# Boost_Converter.net
KiCad netlist of a schematic drawn in Altium Designer
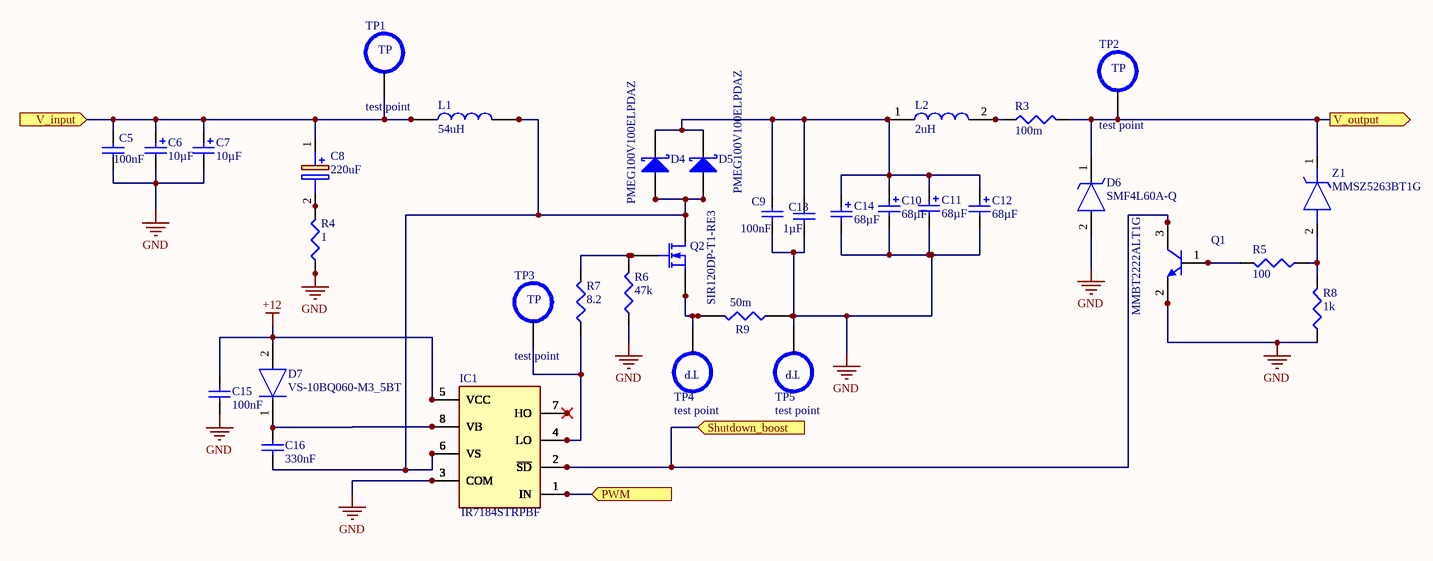
[diagram p0: Boost_Converter.SchDoc]

(export (version "E")
  (design (tool "Eeschema 10.0.6"))
  (components
    (comp (ref "C5")
      (value "100nF")
      (footprint "CAPC3216X180N")
      (description "Capacitor 100nF")
      (fields (field (name "Comment") "CC1206KKX7R0BB104") (field (name "PUBLISHER") "Altium Limited"))
      (libsource (lib "Sch_Capacitors") (part "CC1206KKX7R0BB104"))
    )
    (comp (ref "C6")
      (value "10µF")
      (footprint "870056174001")
      (description "Capacitor Polarised 10uF")
      (fields
        (field (name "MANUFACTURER_PART_NUMBER") "EEV-FK1K101V")
        (field (name "MOUSER PART NUMBER") "667-EEV-FK1K101V")
      )
      (libsource (lib "Sch_Capacitors") (part "870056174001"))
    )
    (comp (ref "C7")
      (value "10µF")
      (footprint "870056174001")
      (description "Capacitor Polarised 10uF")
      (fields
        (field (name "MANUFACTURER_PART_NUMBER") "EEV-FK1K101V")
        (field (name "MOUSER PART NUMBER") "667-EEV-FK1K101V")
      )
      (libsource (lib "Sch_Capacitors") (part "870056174001"))
    )
    (comp (ref "C8")
      (value "220uF")
      (footprint "CAPPRD500W60D1275H2700")
      (description "Capacitor Polarised")
      (fields
        (field (name "MANUFACTURER_PART_NUMBER") "100ZLJ220M12.5X25")
        (field (name "MOUSER PART NUMBER") "232-100ZLJ220M125X25")
      )
      (libsource (lib "Sch_Capacitors") (part "100ZLJ220M12.5X25"))
    )
    (comp (ref "C9")
      (value "100nF")
      (footprint "CAPC3216X180N")
      (description "Capacitor 100nF")
      (fields (field (name "Comment") "CC1206KKX7R0BB104") (field (name "PUBLISHER") "Altium Limited"))
      (libsource (lib "Sch_Capacitors") (part "CC1206KKX7R0BB104"))
    )
    (comp (ref "C10")
      (value "EGXF251ELL680MK30S")
      (footprint "EGXF251ELL680MK30S")
      (description "Capacitor 68uF")
      (fields
        (field (name "MANUFACTURER_PART_NUMBER") "EEV-FK1K101V")
        (field (name "MOUSER PART NUMBER") "667-EEV-FK1K101V")
        (field (name "EGXF251ELL680MK30S") "68µF")
      )
      (libsource (lib "Sch_Capacitors") (part "EGXF251ELL680MK30S"))
    )
    (comp (ref "C11")
      (value "EGXF251ELL680MK30S")
      (footprint "EGXF251ELL680MK30S")
      (description "Capacitor 68uF")
      (fields
        (field (name "MANUFACTURER_PART_NUMBER") "EEV-FK1K101V")
        (field (name "MOUSER PART NUMBER") "667-EEV-FK1K101V")
        (field (name "EGXF251ELL680MK30S") "68µF")
      )
      (libsource (lib "Sch_Capacitors") (part "EGXF251ELL680MK30S"))
    )
    (comp (ref "C12")
      (value "EGXF251ELL680MK30S")
      (footprint "EGXF251ELL680MK30S")
      (description "Capacitor 68uF")
      (fields
        (field (name "MANUFACTURER_PART_NUMBER") "EEV-FK1K101V")
        (field (name "MOUSER PART NUMBER") "667-EEV-FK1K101V")
        (field (name "EGXF251ELL680MK30S") "68µF")
      )
      (libsource (lib "Sch_Capacitors") (part "EGXF251ELL680MK30S"))
    )
    (comp (ref "C13")
      (value "1µF")
      (footprint "CAPC3216X180N")
      (description "Capacitor 1uF")
      (fields (field (name "Comment") "C1206C105M5REC7210") (field (name "PUBLISHER") "Altium Limited"))
      (libsource (lib "Sch_Capacitors") (part "C1206C105M5REC7210"))
    )
    (comp (ref "C14")
      (value "EGXF251ELL680MK30S")
      (footprint "EGXF251ELL680MK30S")
      (description "Capacitor 68uF")
      (fields
        (field (name "MANUFACTURER_PART_NUMBER") "EEV-FK1K101V")
        (field (name "MOUSER PART NUMBER") "667-EEV-FK1K101V")
        (field (name "EGXF251ELL680MK30S") "68µF")
      )
      (libsource (lib "Sch_Capacitors") (part "EGXF251ELL680MK30S"))
    )
    (comp (ref "C15")
      (value "100nF")
      (footprint "CAPC3216X180N")
      (description "Capacitor 100nF")
      (fields (field (name "PUBLISHER") "Altium Limited"))
      (libsource (lib "Sch_Capacitors") (part "CC1206KKX7R0BB104"))
    )
    (comp (ref "C16")
      (value "330nF")
      (footprint "CAPC3216X180N")
      (description "Capacitor 330nF")
      (fields (field (name "PUBLISHER") "Altium Limited"))
      (libsource (lib "Sch_Capacitors") (part "C3216X7R2A334K130AA"))
    )
    (comp (ref "D4")
      (value "PMEG100V100ELPDAZ")
      (footprint "PMEG100V100ELPDAZ")
      (description "Diode")
      (fields (field (name "MOUSER PART NUMBER") "771-MEG100V100ELPDAZ"))
      (libsource (lib "Sch_Diodes") (part "PMEG100V100ELPDAZ"))
    )
    (comp (ref "D5")
      (value "PMEG100V100ELPDAZ")
      (footprint "PMEG100V100ELPDAZ")
      (description "Diode")
      (fields (field (name "MOUSER PART NUMBER") "771-MEG100V100ELPDAZ"))
      (libsource (lib "Sch_Diodes") (part "PMEG100V100ELPDAZ"))
    )
    (comp (ref "D6")
      (value "SMF4L60A-Q")
      (footprint "SODFL3716X135N")
      (description "TVS Diode (Uni-directional)")
      (fields (field (name "MOUSER PART NUMBER") "652-SMF4L60A-Q"))
      (libsource (lib "Sch_Diodes") (part "SMF4L60A-Q"))
    )
    (comp (ref "D7")
      (value "VS-10BQ060-M3_5BT")
      (footprint "DIOM5436X244N")
      (description "Diode")
      (fields
        (field (name "MANUFACTURER_PART_NUMBER") "VS-10BQ060-M3/5BT")
        (field (name "MOUSER PART NUMBER") "78-VS-10BQ060-M35BT")
      )
      (libsource (lib "Sch_Diodes") (part "VS-10BQ060-M3_5BT"))
    )
    (comp (ref "IC1")
      (value "IR7184STRPBF")
      (footprint "SOIC127P600X175-8N")
      (description "Integrated Circuit")
      (fields (field (name "MOUSER PART NUMBER") "942-IR7184STRPBF"))
      (libsource (lib "Sch_IC") (part "IR7184STRPBF"))
    )
    (comp (ref "L1")
      (value "54uH")
      (footprint "SHBC201R7A0054V")
      (description "Inductor 54uH")
      (fields (field (name "Comment") "SHBC20-1R7A0054V"))
      (libsource (lib "Sch_Inductors") (part "SHBC20-1R7A0054V"))
    )
    (comp (ref "L2")
      (value "2uH")
      (footprint "SRP1510CA100M")
      (description "Inductor 2uH")
      (fields
        (field (name "MANUFACTURER_PART_NUMBER") "SRP1038C-100M")
        (field (name "MOUSER PART NUMBER") "652-SRP1038C-100M")
      )
      (libsource (lib "Sch_Inductors") (part "SRP1580CA-2R0M"))
    )
    (comp (ref "Q1")
      (value "MMBT2222ALT1G")
      (footprint "SOT96P237X111-3N")
      (description "NPN transistor")
      (fields (field (name "MOUSER PART NUMBER") "863-MMBT2222ALT1G"))
      (libsource (lib "Sch_Transistors") (part "MMBT2222ALT1G"))
    )
    (comp (ref "Q2")
      (value "SIR120DP-T1-RE3")
      (footprint "SI7141DPT1GE3")
      (description "MOSFET (N-Channel)")
      (fields (field (name "MOUSER PART NUMBER") "78-SIR120DP-T1-RE3"))
      (libsource (lib "Sch_Transistors") (part "SIR120DP-T1-RE3"))
    )
    (comp (ref "R3")
      (value "100m")
      (footprint "RESC6331X80N")
      (description "Resistor 100m")
      (fields (field (name "Comment") "CRM2512-FX-R100ELF") (field (name "PUBLISHER") "Altium Limited"))
      (libsource (lib "Sch_Resistors") (part "CRM2512-FX-R100ELF"))
    )
    (comp (ref "R4")
      (value "1")
      (footprint "RESC6432X120N")
      (description "Resistor 1 3W")
      (fields (field (name "Comment") "35221R0JT") (field (name "PUBLISHER") "Altium Limited"))
      (libsource (lib "Sch_Resistors") (part "35221R0JT"))
    )
    (comp (ref "R5")
      (value "100")
      (footprint "RESC3216X75N")
      (description "Resistor 100")
      (fields (field (name "Comment") "100Ω") (field (name "PUBLISHER") "Altium Limited"))
      (libsource (lib "Sch_Resistors") (part "MCWR12X1000FTL"))
    )
    (comp (ref "R6")
      (value "47k")
      (footprint "RESC3216X75N")
      (description "Resistor 47k")
      (fields (field (name "Comment") "MCWR12X4702FTL") (field (name "PUBLISHER") "Altium Limited"))
      (libsource (lib "Sch_Resistors") (part "MCWR12X4702FTL"))
    )
    (comp (ref "R7")
      (value "8.2")
      (footprint "RESC3216X75N")
      (description "Resistor 8.2")
      (fields (field (name "Comment") "MCWR12W8R20FTL") (field (name "PUBLISHER") "Altium Limited"))
      (libsource (lib "Sch_Resistors") (part "MCWR12W8R20FTL"))
    )
    (comp (ref "R8")
      (value "1k")
      (footprint "RESC3216X75N")
      (description "Resistor 1k")
      (fields (field (name "Comment") "1KΩ") (field (name "PUBLISHER") "Altium Limited"))
      (libsource (lib "Sch_Resistors") (part "MCHP06W2F1001T5E"))
    )
    (comp (ref "R9")
      (value "50m")
      (footprint "RESC7146X175N")
      (description "Resistor 50m")
      (fields
        (field (name "MANUFACTURER_PART_NUMBER") "WSHM2818R0500FEB")
        (field (name "MOUSER PART NUMBER") "71-WSHM2818R0500FEB")
      )
      (libsource (lib "Sch_Resistors") (part "WSHM2818R0500FEB"))
    )
    (comp (ref "TP1")
      (value "test point")
      (footprint "Test point")
      (libsource (lib "Sch_Headers") (part "test point"))
    )
    (comp (ref "TP2")
      (value "test point")
      (footprint "Test point")
      (libsource (lib "Sch_Headers") (part "test point"))
    )
    (comp (ref "TP3")
      (value "test point")
      (footprint "Test point")
      (libsource (lib "Sch_Headers") (part "test point"))
    )
    (comp (ref "TP4")
      (value "test point")
      (footprint "Test point")
      (libsource (lib "Sch_Headers") (part "test point"))
    )
    (comp (ref "TP5")
      (value "test point")
      (footprint "Test point")
      (libsource (lib "Sch_Headers") (part "test point"))
    )
    (comp (ref "Z1")
      (value "MMSZ5263BT1G")
      (footprint "SOD3716X135N")
      (description "Zener Diode")
      (fields (field (name "MOUSER PART NUMBER") "863-MMSZ5263BT1G"))
      (libsource (lib "Sch_Diodes") (part "MMSZ5263BT1G"))
    )
  )
  (nets
    (net (code "1") (name "+12") (class "Default")
      (node (ref "C15") (pin "2") (pinfunction "2_2") (pintype "passive"))
      (node (ref "D7") (pin "2") (pinfunction "A_2") (pintype "passive"))
      (node (ref "IC1") (pin "5") (pinfunction "VCC_5") (pintype "passive"))
    )
    (net (code "2") (name "/PWM") (class "Default")
      (node (ref "IC1") (pin "1") (pinfunction "IN_1") (pintype "passive"))
    )
    (net (code "3") (name "/Shutdown_boost") (class "Default")
      (node (ref "IC1") (pin "2") (pinfunction "~{SD}_2") (pintype "passive"))
      (node (ref "Q1") (pin "3") (pinfunction "C_3") (pintype "passive"))
    )
    (net (code "4") (name "/V_input") (class "Default")
      (node (ref "C5") (pin "1") (pinfunction "1_1") (pintype "passive"))
      (node (ref "C6") (pin "1") (pinfunction "1_1") (pintype "passive"))
      (node (ref "C7") (pin "1") (pinfunction "1_1") (pintype "passive"))
      (node (ref "C8") (pin "1") (pinfunction "+_1") (pintype "passive"))
      (node (ref "L1") (pin "1") (pinfunction "1_1") (pintype "passive"))
      (node (ref "TP1") (pin "5") (pinfunction "5_5") (pintype "passive"))
    )
    (net (code "5") (name "/V_output") (class "Default")
      (node (ref "D6") (pin "1") (pinfunction "K_1") (pintype "passive"))
      (node (ref "R3") (pin "2") (pinfunction "2_2") (pintype "passive"))
      (node (ref "TP2") (pin "5") (pinfunction "5_5") (pintype "passive"))
      (node (ref "Z1") (pin "1") (pinfunction "K_1") (pintype "passive"))
    )
    (net (code "6") (name "GND") (class "Default")
      (node (ref "C10") (pin "2") (pinfunction "2_2") (pintype "passive"))
      (node (ref "C11") (pin "2") (pinfunction "2_2") (pintype "passive"))
      (node (ref "C12") (pin "2") (pinfunction "2_2") (pintype "passive"))
      (node (ref "C13") (pin "1") (pinfunction "1_1") (pintype "passive"))
      (node (ref "C14") (pin "2") (pinfunction "2_2") (pintype "passive"))
      (node (ref "C15") (pin "1") (pinfunction "1_1") (pintype "passive"))
      (node (ref "C5") (pin "2") (pinfunction "2_2") (pintype "passive"))
      (node (ref "C6") (pin "2") (pinfunction "2_2") (pintype "passive"))
      (node (ref "C7") (pin "2") (pinfunction "2_2") (pintype "passive"))
      (node (ref "C9") (pin "2") (pinfunction "2_2") (pintype "passive"))
      (node (ref "D6") (pin "2") (pinfunction "A_2") (pintype "passive"))
      (node (ref "IC1") (pin "3") (pinfunction "COM_3") (pintype "passive"))
      (node (ref "Q1") (pin "2") (pinfunction "E_2") (pintype "passive"))
      (node (ref "R4") (pin "1") (pinfunction "1_1") (pintype "passive"))
      (node (ref "R6") (pin "1") (pinfunction "1_1") (pintype "passive"))
      (node (ref "R8") (pin "1") (pinfunction "1_1") (pintype "passive"))
      (node (ref "R9") (pin "1") (pinfunction "1_1") (pintype "passive"))
      (node (ref "TP5") (pin "5") (pinfunction "5_5") (pintype "passive"))
    )
    (net (code "7") (name "Net-(C8--)") (class "Default")
      (node (ref "C8") (pin "2") (pinfunction "-_2") (pintype "passive"))
      (node (ref "R4") (pin "2") (pinfunction "2_2") (pintype "passive"))
    )
    (net (code "8") (name "Net-(D4-A_1)") (class "Default")
      (node (ref "C16") (pin "1") (pinfunction "1_1") (pintype "passive"))
      (node (ref "D4") (pin "1") (pinfunction "A_1_1") (pintype "passive"))
      (node (ref "D4") (pin "2") (pinfunction "A_2_2") (pintype "passive"))
      (node (ref "D5") (pin "1") (pinfunction "A_1_1") (pintype "passive"))
      (node (ref "D5") (pin "2") (pinfunction "A_2_2") (pintype "passive"))
      (node (ref "IC1") (pin "6") (pinfunction "VS_6") (pintype "passive"))
      (node (ref "L1") (pin "2") (pinfunction "2_2") (pintype "passive"))
      (node (ref "Q2") (pin "5") (pinfunction "D_5") (pintype "passive"))
      (node (ref "Q2") (pin "6") (pinfunction "D_6") (pintype "passive"))
      (node (ref "Q2") (pin "7") (pinfunction "D_7") (pintype "passive"))
      (node (ref "Q2") (pin "8") (pinfunction "D_8") (pintype "passive"))
    )
    (net (code "9") (name "Net-(D4-K)") (class "Default")
      (node (ref "C10") (pin "1") (pinfunction "1_1") (pintype "passive"))
      (node (ref "C11") (pin "1") (pinfunction "1_1") (pintype "passive"))
      (node (ref "C12") (pin "1") (pinfunction "1_1") (pintype "passive"))
      (node (ref "C13") (pin "2") (pinfunction "2_2") (pintype "passive"))
      (node (ref "C14") (pin "1") (pinfunction "1_1") (pintype "passive"))
      (node (ref "C9") (pin "1") (pinfunction "1_1") (pintype "passive"))
      (node (ref "D4") (pin "3") (pinfunction "K_3") (pintype "passive"))
      (node (ref "D5") (pin "3") (pinfunction "K_3") (pintype "passive"))
      (node (ref "L2") (pin "1") (pinfunction "1_1") (pintype "passive"))
    )
    (net (code "10") (name "Net-(D7-K)") (class "Default")
      (node (ref "C16") (pin "2") (pinfunction "2_2") (pintype "passive"))
      (node (ref "D7") (pin "1") (pinfunction "K_1") (pintype "passive"))
      (node (ref "IC1") (pin "8") (pinfunction "VB_8") (pintype "passive"))
    )
    (net (code "11") (name "Net-(IC1-LO)") (class "Default")
      (node (ref "IC1") (pin "4") (pinfunction "LO_4") (pintype "passive"))
      (node (ref "R7") (pin "1") (pinfunction "1_1") (pintype "passive"))
      (node (ref "TP3") (pin "5") (pinfunction "5_5") (pintype "passive"))
    )
    (net (code "12") (name "Net-(L2-Pad2)") (class "Default")
      (node (ref "L2") (pin "2") (pinfunction "2_2") (pintype "passive"))
      (node (ref "R3") (pin "1") (pinfunction "1_1") (pintype "passive"))
    )
    (net (code "13") (name "Net-(Q1-B)") (class "Default")
      (node (ref "Q1") (pin "1") (pinfunction "B_1") (pintype "passive"))
      (node (ref "R5") (pin "2") (pinfunction "2_2") (pintype "passive"))
    )
    (net (code "14") (name "Net-(Q2-G)") (class "Default")
      (node (ref "Q2") (pin "1") (pinfunction "G_1") (pintype "passive"))
      (node (ref "R6") (pin "2") (pinfunction "2_2") (pintype "passive"))
      (node (ref "R7") (pin "2") (pinfunction "2_2") (pintype "passive"))
    )
    (net (code "15") (name "Net-(Q2-S-Pad2)") (class "Default")
      (node (ref "Q2") (pin "2") (pinfunction "S_2") (pintype "passive"))
      (node (ref "Q2") (pin "3") (pinfunction "S_3") (pintype "passive"))
      (node (ref "Q2") (pin "4") (pinfunction "S_4") (pintype "passive"))
      (node (ref "R9") (pin "2") (pinfunction "2_2") (pintype "passive"))
      (node (ref "TP4") (pin "5") (pinfunction "5_5") (pintype "passive"))
    )
    (net (code "16") (name "Net-(Z1-A)") (class "Default")
      (node (ref "R5") (pin "1") (pinfunction "1_1") (pintype "passive"))
      (node (ref "R8") (pin "2") (pinfunction "2_2") (pintype "passive"))
      (node (ref "Z1") (pin "2") (pinfunction "A_2") (pintype "passive"))
    )
    (net (code "17") (name "unconnected-(IC1-HO-Pad7)") (class "Default")
      (node (ref "IC1") (pin "7") (pinfunction "HO_7") (pintype "passive+no_connect"))
    )
  )
)
